# microcontroller.net
KiCad netlist of a schematic drawn in Altium Designer
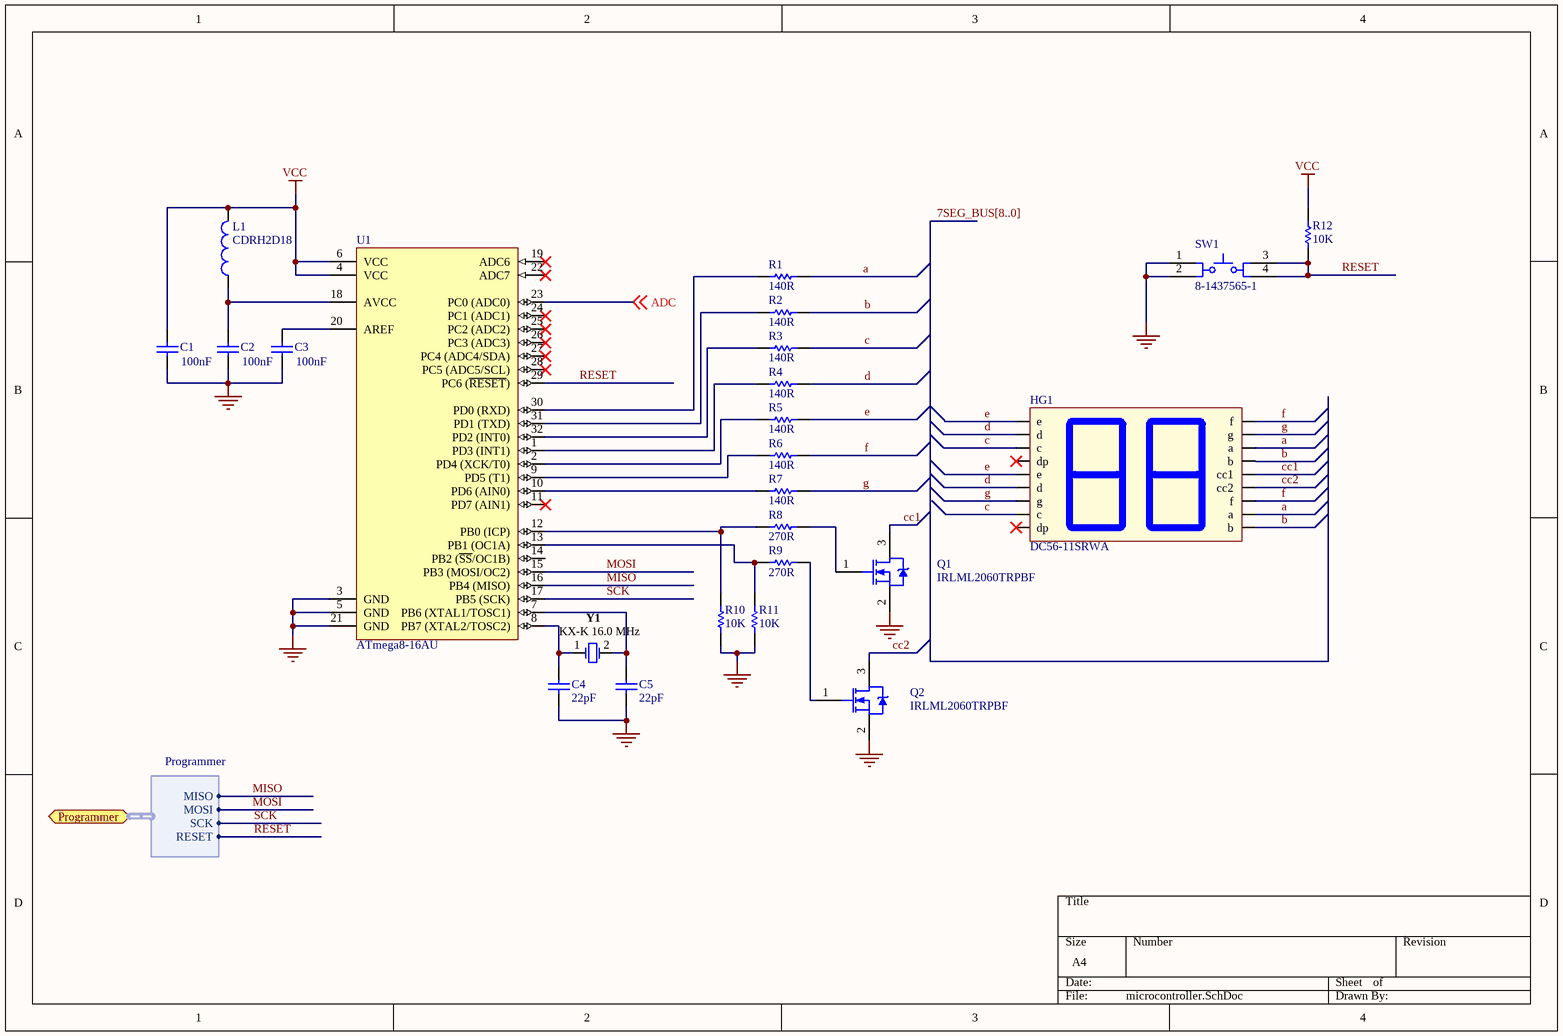
[diagram p0: microcontroller.SchDoc]

(export (version "E")
  (design (tool "Eeschema 10.0.6"))
  (components
    (comp (ref "C1")
      (value "100nF")
      (footprint "CAPC0805(2012)75_M")
      (description "CAP 100nF 16V ±20% 0805 (2012 Metric) Thickness 0.75mm SMD")
      (fields (field (name "TOLERANCE") "Â±20%"))
      (libsource (lib "Altium Content Vault") (part "CMP-1036-04403-1"))
    )
    (comp (ref "C2")
      (value "100nF")
      (footprint "CAPC0805(2012)75_M")
      (description "CAP 100nF 16V ±20% 0805 (2012 Metric) Thickness 0.75mm SMD")
      (fields (field (name "TOLERANCE") "Â±20%"))
      (libsource (lib "Altium Content Vault") (part "CMP-1036-04403-1"))
    )
    (comp (ref "C3")
      (value "100nF")
      (footprint "CAPC0805(2012)75_M")
      (description "CAP 100nF 16V ±20% 0805 (2012 Metric) Thickness 0.75mm SMD")
      (fields (field (name "TOLERANCE") "Â±20%"))
      (libsource (lib "Altium Content Vault") (part "CMP-1036-04403-1"))
    )
    (comp (ref "C4")
      (value "22pF")
      (footprint "CAPC0805(2012)100_M")
      (description "CAP 22pF 16V ±0.25pF 0805 (2012 Metric) Thickness 1mm SMD")
      (fields (field (name "TOLERANCE") "Â±0.25pF"))
      (libsource (lib "Altium Content Vault") (part "CMP-1036-01214-1"))
    )
    (comp (ref "C5")
      (value "22pF")
      (footprint "CAPC0805(2012)100_M")
      (description "CAP 22pF 16V ±0.25pF 0805 (2012 Metric) Thickness 1mm SMD")
      (fields (field (name "TOLERANCE") "Â±0.25pF"))
      (libsource (lib "Altium Content Vault") (part "CMP-1036-01214-1"))
    )
    (comp (ref "HG1")
      (value "DC56-11SRWA")
      (footprint "library pcb:7seg_LCD")
      (libsource (lib "library") (part "Component_1"))
    )
    (comp (ref "L1")
      (value "CDRH2D18")
      (footprint "SUMI-CDRH2D14NP-1R5NC-2_V")
      (description "Power Inductor,-40 to 100 degC, 3.2 x 3.2 x 1.55 mm, SMD")
      (fields (field (name "PARTNUMBER") "CDRH2D14NP-1R5NC") (field (name "MANUFACTURER") "Sumida"))
      (libsource (lib "Altium Content Vault") (part "CMP-0468-00001-2"))
    )
    (comp (ref "Q1")
      (value "IRLML2060TRPBF")
      (footprint "INTR-IRLML2402TRPBF-3_V")
      (description "HEXFET(R) Power MOSFET, N-Channel, 20 V, 1.2 A, 3-Pin SOT-23, RoHS, Tape and Reel")
      (fields (field (name "MANUFACTURER") "International Rectifier"))
      (libsource (lib "Altium Content Vault") (part "CMP-2000-05155-1"))
    )
    (comp (ref "Q2")
      (value "IRLML2060TRPBF")
      (footprint "INTR-IRLML2402TRPBF-3_V")
      (description "HEXFET(R) Power MOSFET, N-Channel, 20 V, 1.2 A, 3-Pin SOT-23, RoHS, Tape and Reel")
      (fields (field (name "MANUFACTURER") "International Rectifier"))
      (libsource (lib "Altium Content Vault") (part "CMP-2000-05155-1"))
    )
    (comp (ref "R1")
      (value "140R")
      (footprint "RESC0805(2012)_M")
      (description "140R 0.125W 1% 0805 (2012 Metric)  SMD")
      (fields (field (name "POWER") "0.125 W") (field (name "TOLERANCE") "1 %"))
      (libsource (lib "Altium Content Vault") (part "CMP-1013-00412-1"))
    )
    (comp (ref "R2")
      (value "140R")
      (footprint "RESC0805(2012)_M")
      (description "140R 0.125W 1% 0805 (2012 Metric)  SMD")
      (fields (field (name "POWER") "0.125 W") (field (name "TOLERANCE") "1 %"))
      (libsource (lib "Altium Content Vault") (part "RES"))
    )
    (comp (ref "R3")
      (value "140R")
      (footprint "RESC0805(2012)_M")
      (description "140R 0.125W 1% 0805 (2012 Metric)  SMD")
      (fields (field (name "POWER") "0.125 W") (field (name "TOLERANCE") "1 %"))
      (libsource (lib "Altium Content Vault") (part "RES"))
    )
    (comp (ref "R4")
      (value "140R")
      (footprint "RESC0805(2012)_M")
      (description "140R 0.125W 1% 0805 (2012 Metric)  SMD")
      (fields (field (name "POWER") "0.125 W") (field (name "TOLERANCE") "1 %"))
      (libsource (lib "Altium Content Vault") (part "RES"))
    )
    (comp (ref "R5")
      (value "140R")
      (footprint "RESC0805(2012)_M")
      (description "140R 0.125W 1% 0805 (2012 Metric)  SMD")
      (fields (field (name "POWER") "0.125 W") (field (name "TOLERANCE") "1 %"))
      (libsource (lib "Altium Content Vault") (part "RES"))
    )
    (comp (ref "R6")
      (value "140R")
      (footprint "RESC0805(2012)_M")
      (description "140R 0.125W 1% 0805 (2012 Metric)  SMD")
      (fields (field (name "POWER") "0.125 W") (field (name "TOLERANCE") "1 %"))
      (libsource (lib "Altium Content Vault") (part "RES"))
    )
    (comp (ref "R7")
      (value "140R")
      (footprint "RESC0805(2012)_M")
      (description "140R 0.125W 1% 0805 (2012 Metric)  SMD")
      (fields (field (name "POWER") "0.125 W") (field (name "TOLERANCE") "1 %"))
      (libsource (lib "Altium Content Vault") (part "RES"))
    )
    (comp (ref "R8")
      (value "270R")
      (footprint "RESC0805(2012)_M")
      (description "270R 0.125W 5% 0805 (2012 Metric)  SMD")
      (fields (field (name "POWER") "0.125 W") (field (name "TOLERANCE") "5 %"))
      (libsource (lib "Altium Content Vault") (part "CMP-1013-00060-1"))
    )
    (comp (ref "R9")
      (value "270R")
      (footprint "RESC0805(2012)_M")
      (description "270R 0.125W 5% 0805 (2012 Metric)  SMD")
      (fields (field (name "POWER") "0.125 W") (field (name "TOLERANCE") "5 %"))
      (libsource (lib "Altium Content Vault") (part "CMP-1013-00060-1"))
    )
    (comp (ref "R10")
      (value "10K")
      (footprint "RESC0805(2012)_M")
      (description "10K 0.125W 5% 0805 (2012 Metric)  SMD")
      (fields (field (name "POWER") "0.125 W") (field (name "TOLERANCE") "5 %"))
      (libsource (lib "Altium Content Vault") (part "CMP-1013-00098-1"))
    )
    (comp (ref "R11")
      (value "10K")
      (footprint "RESC0805(2012)_M")
      (description "10K 0.125W 5% 0805 (2012 Metric)  SMD")
      (fields (field (name "POWER") "0.125 W") (field (name "TOLERANCE") "5 %"))
      (libsource (lib "Altium Content Vault") (part "CMP-1013-00098-1"))
    )
    (comp (ref "R12")
      (value "10K")
      (footprint "RESC0805(2012)_M")
      (description "10K 0.125W 5% 0805 (2012 Metric)  SMD")
      (fields (field (name "POWER") "0.125 W") (field (name "TOLERANCE") "5 %"))
      (libsource (lib "Altium Content Vault") (part "CMP-1013-00098-1"))
    )
    (comp (ref "SW1")
      (value "8-1437565-1")
      (footprint "library pcb:SW-SPST-NO-4")
      (libsource (lib "library") (part "SW-SPST-NO-4"))
    )
    (comp (ref "U1")
      (value "ATmega8-16AU")
      (footprint "32A_L")
      (libsource (lib "Altium Content Vault") (part "MC-8B-AT8L-SQ32A"))
    )
    (comp (ref "Y1")
      (value "KX-K 16.0 MHz")
      (footprint "FOX-HC49SDLF_V")
      (description "Resistance Weld Crystal, 8 MHz, +/- 30 ppm, -20 to 70 degC, 2-Pin SMD, RoHS, Tape and Reel")
      (fields (field (name "MANUFACTURER") "FOX Electronics") (field (name "TOLERANCE") "50ppm"))
      (libsource (lib "Altium Content Vault") (part "CMP-2100-03639-1"))
    )
  )
  (nets
    (net (code "12") (name "/MISO") (class "Default")
      (node (ref "U1") (pin "16") (pinfunction "PB4_(MISO)_16") (pintype "bidirectional"))
    )
    (net (code "13") (name "/MOSI") (class "Default")
      (node (ref "U1") (pin "15") (pinfunction "PB3_(MOSI/OC2)_15") (pintype "bidirectional"))
    )
    (net (code "14") (name "/RESET") (class "Default")
      (node (ref "R12") (pin "1") (pinfunction "1_1") (pintype "passive"))
      (node (ref "SW1") (pin "3") (pinfunction "3_3") (pintype "passive"))
      (node (ref "SW1") (pin "4") (pinfunction "4_4") (pintype "passive"))
      (node (ref "U1") (pin "29") (pinfunction "PC6_(~{RESET})_29") (pintype "bidirectional"))
    )
    (net (code "15") (name "/SCK") (class "Default")
      (node (ref "U1") (pin "17") (pinfunction "PB5_(SCK)_17") (pintype "bidirectional"))
    )
    (net (code "16") (name "/a") (class "Default")
      (node (ref "HG1") (pin "11") (pinfunction "a_11") (pintype "passive"))
      (node (ref "HG1") (pin "16") (pinfunction "a_16") (pintype "passive"))
      (node (ref "R1") (pin "2") (pinfunction "2_2") (pintype "passive"))
    )
    (net (code "17") (name "/b") (class "Default")
      (node (ref "HG1") (pin "10") (pinfunction "b_10") (pintype "passive"))
      (node (ref "HG1") (pin "15") (pinfunction "b_15") (pintype "passive"))
      (node (ref "R2") (pin "2") (pinfunction "2_2") (pintype "passive"))
    )
    (net (code "18") (name "/c") (class "Default")
      (node (ref "HG1") (pin "3") (pinfunction "c_3") (pintype "passive"))
      (node (ref "HG1") (pin "8") (pinfunction "c_8") (pintype "passive"))
      (node (ref "R3") (pin "2") (pinfunction "2_2") (pintype "passive"))
    )
    (net (code "19") (name "/cc1") (class "Default")
      (node (ref "HG1") (pin "14") (pinfunction "cc1_14") (pintype "passive"))
      (node (ref "Q1") (pin "3") (pinfunction "D_3") (pintype "passive"))
    )
    (net (code "20") (name "/cc2") (class "Default")
      (node (ref "HG1") (pin "13") (pinfunction "cc2_13") (pintype "passive"))
      (node (ref "Q2") (pin "3") (pinfunction "D_3") (pintype "passive"))
    )
    (net (code "21") (name "/d") (class "Default")
      (node (ref "HG1") (pin "2") (pinfunction "d_2") (pintype "passive"))
      (node (ref "HG1") (pin "6") (pinfunction "d_6") (pintype "passive"))
      (node (ref "R4") (pin "2") (pinfunction "2_2") (pintype "passive"))
    )
    (net (code "22") (name "/e") (class "Default")
      (node (ref "HG1") (pin "1") (pinfunction "e_1") (pintype "passive"))
      (node (ref "HG1") (pin "5") (pinfunction "e_5") (pintype "passive"))
      (node (ref "R5") (pin "2") (pinfunction "2_2") (pintype "passive"))
    )
    (net (code "23") (name "/f") (class "Default")
      (node (ref "HG1") (pin "12") (pinfunction "f_12") (pintype "passive"))
      (node (ref "HG1") (pin "18") (pinfunction "f_18") (pintype "passive"))
      (node (ref "R6") (pin "2") (pinfunction "2_2") (pintype "passive"))
    )
    (net (code "24") (name "/g") (class "Default")
      (node (ref "HG1") (pin "17") (pinfunction "g_17") (pintype "passive"))
      (node (ref "HG1") (pin "7") (pinfunction "g_7") (pintype "passive"))
      (node (ref "R7") (pin "2") (pinfunction "2_2") (pintype "passive"))
    )
    (net (code "26") (name "ADC") (class "Default")
      (node (ref "U1") (pin "23") (pinfunction "PC0_(ADC0)_23") (pintype "bidirectional"))
    )
    (net (code "27") (name "GND") (class "Default")
      (node (ref "C1") (pin "1") (pinfunction "1_1") (pintype "passive"))
      (node (ref "C2") (pin "1") (pinfunction "1_1") (pintype "passive"))
      (node (ref "C3") (pin "1") (pinfunction "1_1") (pintype "passive"))
      (node (ref "C4") (pin "1") (pinfunction "1_1") (pintype "passive"))
      (node (ref "C5") (pin "1") (pinfunction "1_1") (pintype "passive"))
      (node (ref "Q1") (pin "2") (pinfunction "S_2") (pintype "passive"))
      (node (ref "Q2") (pin "2") (pinfunction "S_2") (pintype "passive"))
      (node (ref "R10") (pin "1") (pinfunction "1_1") (pintype "passive"))
      (node (ref "R11") (pin "1") (pinfunction "1_1") (pintype "passive"))
      (node (ref "SW1") (pin "1") (pinfunction "1_1") (pintype "passive"))
      (node (ref "SW1") (pin "2") (pinfunction "2_2") (pintype "passive"))
      (node (ref "U1") (pin "21") (pinfunction "GND_21") (pintype "power_in"))
      (node (ref "U1") (pin "3") (pinfunction "GND_3") (pintype "power_in"))
      (node (ref "U1") (pin "5") (pinfunction "GND_5") (pintype "power_in"))
    )
    (net (code "28") (name "Net-(Q1-G)") (class "Default")
      (node (ref "Q1") (pin "1") (pinfunction "G_1") (pintype "passive"))
      (node (ref "R8") (pin "2") (pinfunction "2_2") (pintype "passive"))
    )
    (net (code "29") (name "Net-(Q2-G)") (class "Default")
      (node (ref "Q2") (pin "1") (pinfunction "G_1") (pintype "passive"))
      (node (ref "R9") (pin "2") (pinfunction "2_2") (pintype "passive"))
    )
    (net (code "30") (name "Net-(U1-AREF)") (class "Default")
      (node (ref "C3") (pin "2") (pinfunction "2_2") (pintype "passive"))
      (node (ref "U1") (pin "20") (pinfunction "AREF_20") (pintype "passive"))
    )
    (net (code "31") (name "Net-(U1-AVCC)") (class "Default")
      (node (ref "C2") (pin "2") (pinfunction "2_2") (pintype "passive"))
      (node (ref "L1") (pin "1") (pinfunction "1_1") (pintype "passive"))
      (node (ref "U1") (pin "18") (pinfunction "AVCC_18") (pintype "power_in"))
    )
    (net (code "32") (name "Net-(U1-PB0_(ICP))") (class "Default")
      (node (ref "R10") (pin "2") (pinfunction "2_2") (pintype "passive"))
      (node (ref "R8") (pin "1") (pinfunction "1_1") (pintype "passive"))
      (node (ref "U1") (pin "12") (pinfunction "PB0_(ICP)_12") (pintype "bidirectional"))
    )
    (net (code "33") (name "Net-(U1-PB1_(OC1A))") (class "Default")
      (node (ref "R11") (pin "2") (pinfunction "2_2") (pintype "passive"))
      (node (ref "R9") (pin "1") (pinfunction "1_1") (pintype "passive"))
      (node (ref "U1") (pin "13") (pinfunction "PB1_(OC1A)_13") (pintype "bidirectional"))
    )
    (net (code "34") (name "Net-(U1-PB6_(XTAL1{slash}TOSC1))") (class "Default")
      (node (ref "C5") (pin "2") (pinfunction "2_2") (pintype "passive"))
      (node (ref "U1") (pin "7") (pinfunction "PB6_(XTAL1/TOSC1)_7") (pintype "bidirectional"))
      (node (ref "Y1") (pin "2") (pinfunction "2_2") (pintype "passive"))
    )
    (net (code "35") (name "Net-(U1-PB7_(XTAL2{slash}TOSC2))") (class "Default")
      (node (ref "C4") (pin "2") (pinfunction "2_2") (pintype "passive"))
      (node (ref "U1") (pin "8") (pinfunction "PB7_(XTAL2/TOSC2)_8") (pintype "bidirectional"))
      (node (ref "Y1") (pin "1") (pinfunction "1_1") (pintype "passive"))
    )
    (net (code "36") (name "Net-(U1-PD0_(RXD))") (class "Default")
      (node (ref "R1") (pin "1") (pinfunction "1_1") (pintype "passive"))
      (node (ref "U1") (pin "30") (pinfunction "PD0_(RXD)_30") (pintype "bidirectional"))
    )
    (net (code "37") (name "Net-(U1-PD1_(TXD))") (class "Default")
      (node (ref "R2") (pin "1") (pinfunction "1_1") (pintype "passive"))
      (node (ref "U1") (pin "31") (pinfunction "PD1_(TXD)_31") (pintype "bidirectional"))
    )
    (net (code "38") (name "Net-(U1-PD2_(INT0))") (class "Default")
      (node (ref "R3") (pin "1") (pinfunction "1_1") (pintype "passive"))
      (node (ref "U1") (pin "32") (pinfunction "PD2_(INT0)_32") (pintype "bidirectional"))
    )
    (net (code "39") (name "Net-(U1-PD3_(INT1))") (class "Default")
      (node (ref "R4") (pin "1") (pinfunction "1_1") (pintype "passive"))
      (node (ref "U1") (pin "1") (pinfunction "PD3_(INT1)_1") (pintype "bidirectional"))
    )
    (net (code "40") (name "Net-(U1-PD4_(XCK{slash}T0))") (class "Default")
      (node (ref "R5") (pin "1") (pinfunction "1_1") (pintype "passive"))
      (node (ref "U1") (pin "2") (pinfunction "PD4_(XCK/T0)_2") (pintype "bidirectional"))
    )
    (net (code "41") (name "Net-(U1-PD5_(T1))") (class "Default")
      (node (ref "R6") (pin "1") (pinfunction "1_1") (pintype "passive"))
      (node (ref "U1") (pin "9") (pinfunction "PD5_(T1)_9") (pintype "bidirectional"))
    )
    (net (code "42") (name "Net-(U1-PD6_(AIN0))") (class "Default")
      (node (ref "R7") (pin "1") (pinfunction "1_1") (pintype "passive"))
      (node (ref "U1") (pin "10") (pinfunction "PD6_(AIN0)_10") (pintype "bidirectional"))
    )
    (net (code "43") (name "VCC") (class "Default")
      (node (ref "C1") (pin "2") (pinfunction "2_2") (pintype "passive"))
      (node (ref "L1") (pin "2") (pinfunction "2_2") (pintype "passive"))
      (node (ref "R12") (pin "2") (pinfunction "2_2") (pintype "passive"))
      (node (ref "U1") (pin "4") (pinfunction "VCC_4") (pintype "power_in"))
      (node (ref "U1") (pin "6") (pinfunction "VCC_6") (pintype "power_in"))
    )
    (net (code "44") (name "unconnected-(HG1-dp-Pad4)") (class "Default")
      (node (ref "HG1") (pin "4") (pinfunction "dp_4") (pintype "passive+no_connect"))
    )
    (net (code "45") (name "unconnected-(HG1-dp-Pad9)") (class "Default")
      (node (ref "HG1") (pin "9") (pinfunction "dp_9") (pintype "passive+no_connect"))
    )
    (net (code "46") (name "unconnected-(U1-ADC6-Pad19)") (class "Default")
      (node (ref "U1") (pin "19") (pinfunction "ADC6_19") (pintype "input+no_connect"))
    )
    (net (code "47") (name "unconnected-(U1-ADC7-Pad22)") (class "Default")
      (node (ref "U1") (pin "22") (pinfunction "ADC7_22") (pintype "input+no_connect"))
    )
    (net (code "48") (name "unconnected-(U1-PB2_(~{SS}{slash}OC1B)-Pad14)") (class "Default")
      (node (ref "U1") (pin "14") (pinfunction "PB2_(~{SS}/OC1B)_14") (pintype "bidirectional"))
    )
    (net (code "49") (name "unconnected-(U1-PC1_(ADC1)-Pad24)") (class "Default")
      (node (ref "U1") (pin "24") (pinfunction "PC1_(ADC1)_24") (pintype "bidirectional+no_connect"))
    )
    (net (code "50") (name "unconnected-(U1-PC2_(ADC2)-Pad25)") (class "Default")
      (node (ref "U1") (pin "25") (pinfunction "PC2_(ADC2)_25") (pintype "bidirectional+no_connect"))
    )
    (net (code "51") (name "unconnected-(U1-PC3_(ADC3)-Pad26)") (class "Default")
      (node (ref "U1") (pin "26") (pinfunction "PC3_(ADC3)_26") (pintype "bidirectional+no_connect"))
    )
    (net (code "52") (name "unconnected-(U1-PC4_(ADC4{slash}SDA)-Pad27)") (class "Default")
      (node (ref "U1") (pin "27") (pinfunction "PC4_(ADC4/SDA)_27") (pintype "bidirectional+no_connect"))
    )
    (net (code "53") (name "unconnected-(U1-PC5_(ADC5{slash}SCL)-Pad28)") (class "Default")
      (node (ref "U1") (pin "28") (pinfunction "PC5_(ADC5/SCL)_28") (pintype "bidirectional+no_connect"))
    )
    (net (code "54") (name "unconnected-(U1-PD7_(AIN1)-Pad11)") (class "Default")
      (node (ref "U1") (pin "11") (pinfunction "PD7_(AIN1)_11") (pintype "bidirectional+no_connect"))
    )
  )
)
